# SCH.net
KiCad netlist of a schematic drawn in Altium Designer
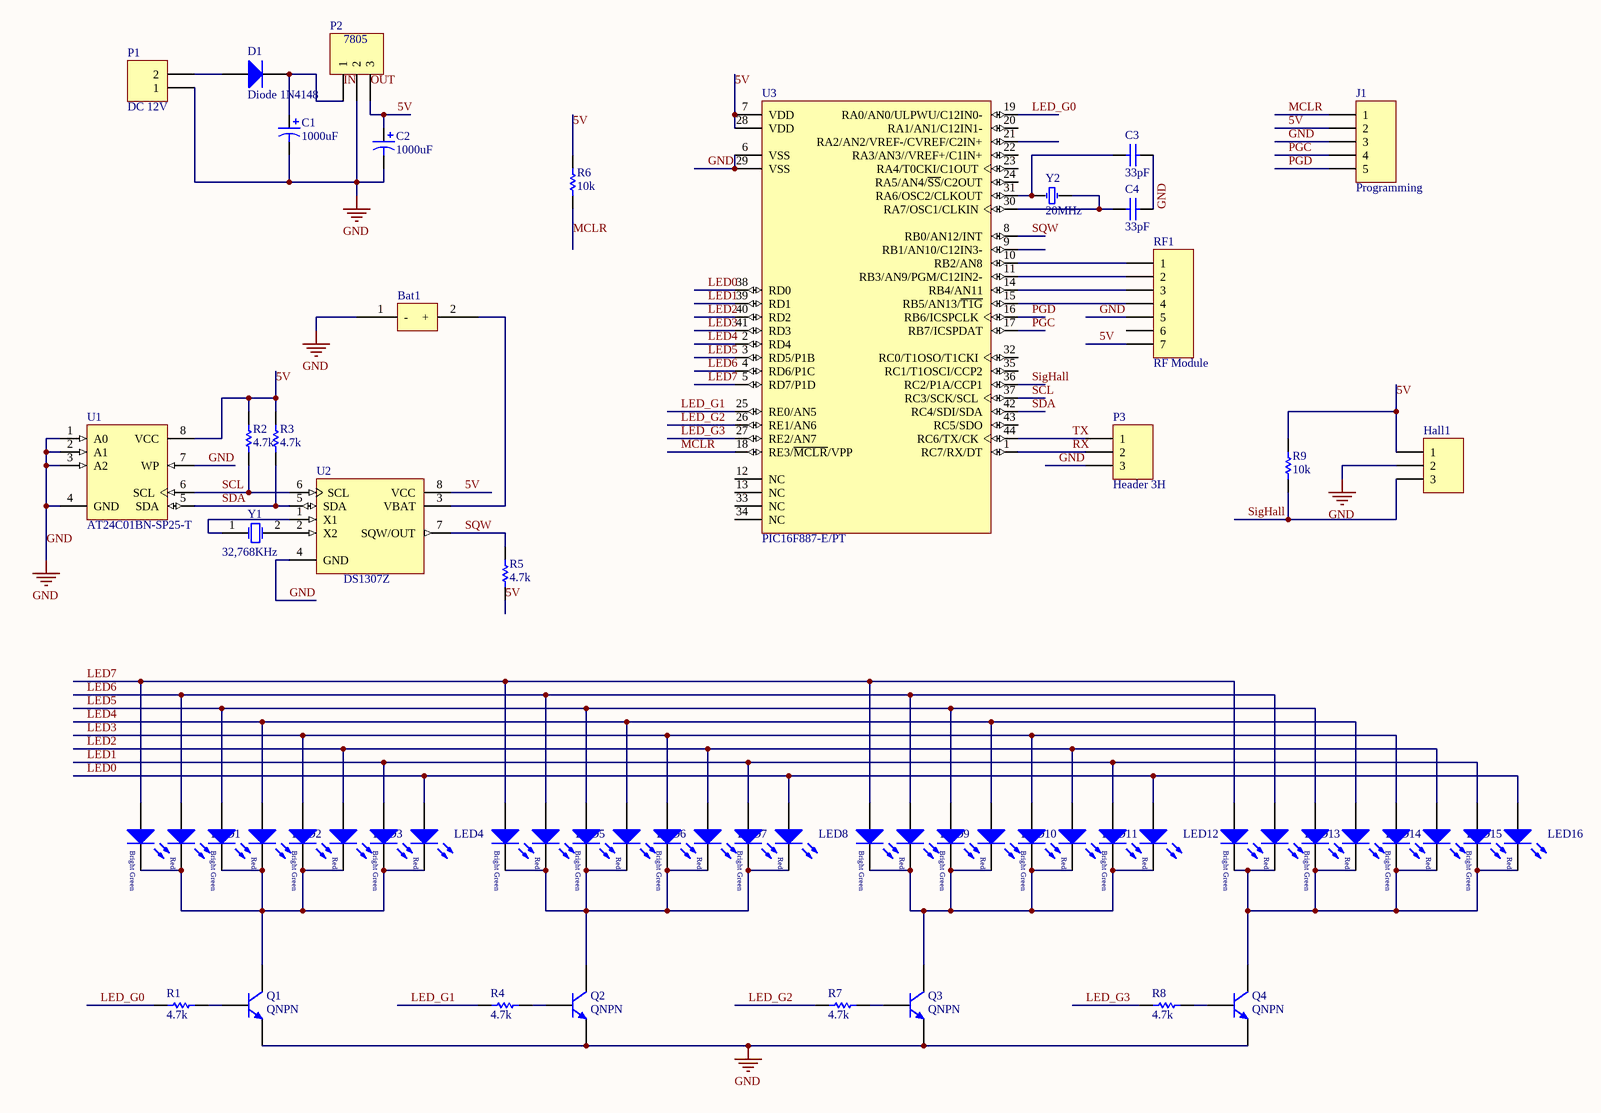
[diagram p0: SCH.SchDoc]

(export (version "E")
  (design (tool "Eeschema 10.0.6"))
  (components
    (comp (ref "Bat1") (value "Battery") (footprint "BATTERY") (libsource (lib "Battery") (part "Battery")))
    (comp (ref "C1")
      (value "1000uF")
      (footprint "CAP POL 2")
      (description "Polarized Capacitor (Surface Mount)")
      (fields (field (name "Comment") "Cap Pol3") (field (name "PUBLISHER") "Altium Limited"))
      (libsource (lib "Miscellaneous Devices") (part "Cap Pol3"))
    )
    (comp (ref "C2")
      (value "1000uF")
      (footprint "CAP POL 2")
      (description "Polarized Capacitor (Surface Mount)")
      (fields (field (name "Comment") "Cap Pol3") (field (name "PUBLISHER") "Altium Limited"))
      (libsource (lib "Miscellaneous Devices") (part "Cap Pol3"))
    )
    (comp (ref "C3")
      (value "33pF")
      (footprint "SM/C_0805")
      (description "Capacitor (Semiconductor SIM Model)")
      (fields (field (name "Comment") "Cap Semi") (field (name "PUBLISHER") "Altium Limited"))
      (libsource (lib "Miscellaneous Devices") (part "Cap Semi"))
    )
    (comp (ref "C4")
      (value "33pF")
      (footprint "SM/C_0805")
      (description "Capacitor (Semiconductor SIM Model)")
      (fields (field (name "Comment") "Cap Semi") (field (name "PUBLISHER") "Altium Limited"))
      (libsource (lib "Miscellaneous Devices") (part "Cap Semi"))
    )
    (comp (ref "D1")
      (value "Diode 1N4148")
      (footprint "DO-35")
      (description "High Conductance Fast Diode")
      (fields (field (name "PUBLISHER") "Altium Limited"))
      (libsource (lib "Miscellaneous Devices") (part "Diode 1N4148"))
    )
    (comp (ref "Hall1")
      (value "Header 3")
      (footprint "HDR1X3")
      (description "Header, 3-Pin")
      (fields (field (name "PUBLISHER") "Altium Limited"))
      (libsource (lib "Miscellaneous Connectors") (part "Header 3"))
    )
    (comp (ref "J1")
      (value "Programming")
      (footprint "HDR1X5H")
      (description "Header, 5-Pin, Right Angle")
      (fields (field (name "PUBLISHER") "Altium Limited"))
      (libsource (lib "Miscellaneous Connectors") (part "Header 5H"))
    )
    (comp (ref "LED1")
      (value "150141RV73100")
      (footprint "3528")
      (description "SMD Bi-Color Top LED, WL-SBTW, Red & Bright Green")
      (fields
        (field (name "MANUFACTURER") "Würth Elektronik eiSos GmbH")
        (field (name "CREATED BY") "Christin Otto")
      )
      (libsource (lib "Altium_WE_eiSos_WL-SBTW") (part "WL-SBTW 3528 150141RV73100"))
    )
    (comp (ref "LED2")
      (value "150141RV73100")
      (footprint "3528")
      (description "SMD Bi-Color Top LED, WL-SBTW, Red & Bright Green")
      (fields
        (field (name "MANUFACTURER") "Würth Elektronik eiSos GmbH")
        (field (name "CREATED BY") "Christin Otto")
      )
      (libsource (lib "Altium_WE_eiSos_WL-SBTW") (part "WL-SBTW 3528 150141RV73100"))
    )
    (comp (ref "LED3")
      (value "150141RV73100")
      (footprint "3528")
      (description "SMD Bi-Color Top LED, WL-SBTW, Red & Bright Green")
      (fields
        (field (name "MANUFACTURER") "Würth Elektronik eiSos GmbH")
        (field (name "CREATED BY") "Christin Otto")
      )
      (libsource (lib "Altium_WE_eiSos_WL-SBTW") (part "WL-SBTW 3528 150141RV73100"))
    )
    (comp (ref "LED4")
      (value "150141RV73100")
      (footprint "3528")
      (description "SMD Bi-Color Top LED, WL-SBTW, Red & Bright Green")
      (fields
        (field (name "MANUFACTURER") "Würth Elektronik eiSos GmbH")
        (field (name "CREATED BY") "Christin Otto")
      )
      (libsource (lib "Altium_WE_eiSos_WL-SBTW") (part "WL-SBTW 3528 150141RV73100"))
    )
    (comp (ref "LED5")
      (value "150141RV73100")
      (footprint "3528")
      (description "SMD Bi-Color Top LED, WL-SBTW, Red & Bright Green")
      (fields
        (field (name "MANUFACTURER") "Würth Elektronik eiSos GmbH")
        (field (name "CREATED BY") "Christin Otto")
      )
      (libsource (lib "Altium_WE_eiSos_WL-SBTW") (part "WL-SBTW 3528 150141RV73100"))
    )
    (comp (ref "LED6")
      (value "150141RV73100")
      (footprint "3528")
      (description "SMD Bi-Color Top LED, WL-SBTW, Red & Bright Green")
      (fields
        (field (name "MANUFACTURER") "Würth Elektronik eiSos GmbH")
        (field (name "CREATED BY") "Christin Otto")
      )
      (libsource (lib "Altium_WE_eiSos_WL-SBTW") (part "WL-SBTW 3528 150141RV73100"))
    )
    (comp (ref "LED7")
      (value "150141RV73100")
      (footprint "3528")
      (description "SMD Bi-Color Top LED, WL-SBTW, Red & Bright Green")
      (fields
        (field (name "MANUFACTURER") "Würth Elektronik eiSos GmbH")
        (field (name "CREATED BY") "Christin Otto")
      )
      (libsource (lib "Altium_WE_eiSos_WL-SBTW") (part "WL-SBTW 3528 150141RV73100"))
    )
    (comp (ref "LED8")
      (value "150141RV73100")
      (footprint "3528")
      (description "SMD Bi-Color Top LED, WL-SBTW, Red & Bright Green")
      (fields
        (field (name "MANUFACTURER") "Würth Elektronik eiSos GmbH")
        (field (name "CREATED BY") "Christin Otto")
      )
      (libsource (lib "Altium_WE_eiSos_WL-SBTW") (part "WL-SBTW 3528 150141RV73100"))
    )
    (comp (ref "LED9")
      (value "150141RV73100")
      (footprint "3528")
      (description "SMD Bi-Color Top LED, WL-SBTW, Red & Bright Green")
      (fields
        (field (name "MANUFACTURER") "Würth Elektronik eiSos GmbH")
        (field (name "CREATED BY") "Christin Otto")
      )
      (libsource (lib "Altium_WE_eiSos_WL-SBTW") (part "WL-SBTW 3528 150141RV73100"))
    )
    (comp (ref "LED10")
      (value "150141RV73100")
      (footprint "3528")
      (description "SMD Bi-Color Top LED, WL-SBTW, Red & Bright Green")
      (fields
        (field (name "MANUFACTURER") "Würth Elektronik eiSos GmbH")
        (field (name "CREATED BY") "Christin Otto")
      )
      (libsource (lib "Altium_WE_eiSos_WL-SBTW") (part "WL-SBTW 3528 150141RV73100"))
    )
    (comp (ref "LED11")
      (value "150141RV73100")
      (footprint "3528")
      (description "SMD Bi-Color Top LED, WL-SBTW, Red & Bright Green")
      (fields
        (field (name "MANUFACTURER") "Würth Elektronik eiSos GmbH")
        (field (name "CREATED BY") "Christin Otto")
      )
      (libsource (lib "Altium_WE_eiSos_WL-SBTW") (part "WL-SBTW 3528 150141RV73100"))
    )
    (comp (ref "LED12")
      (value "150141RV73100")
      (footprint "3528")
      (description "SMD Bi-Color Top LED, WL-SBTW, Red & Bright Green")
      (fields
        (field (name "MANUFACTURER") "Würth Elektronik eiSos GmbH")
        (field (name "CREATED BY") "Christin Otto")
      )
      (libsource (lib "Altium_WE_eiSos_WL-SBTW") (part "WL-SBTW 3528 150141RV73100"))
    )
    (comp (ref "LED13")
      (value "150141RV73100")
      (footprint "3528")
      (description "SMD Bi-Color Top LED, WL-SBTW, Red & Bright Green")
      (fields
        (field (name "MANUFACTURER") "Würth Elektronik eiSos GmbH")
        (field (name "CREATED BY") "Christin Otto")
      )
      (libsource (lib "Altium_WE_eiSos_WL-SBTW") (part "WL-SBTW 3528 150141RV73100"))
    )
    (comp (ref "LED14")
      (value "150141RV73100")
      (footprint "3528")
      (description "SMD Bi-Color Top LED, WL-SBTW, Red & Bright Green")
      (fields
        (field (name "MANUFACTURER") "Würth Elektronik eiSos GmbH")
        (field (name "CREATED BY") "Christin Otto")
      )
      (libsource (lib "Altium_WE_eiSos_WL-SBTW") (part "WL-SBTW 3528 150141RV73100"))
    )
    (comp (ref "LED15")
      (value "150141RV73100")
      (footprint "3528")
      (description "SMD Bi-Color Top LED, WL-SBTW, Red & Bright Green")
      (fields
        (field (name "MANUFACTURER") "Würth Elektronik eiSos GmbH")
        (field (name "CREATED BY") "Christin Otto")
      )
      (libsource (lib "Altium_WE_eiSos_WL-SBTW") (part "WL-SBTW 3528 150141RV73100"))
    )
    (comp (ref "LED16")
      (value "150141RV73100")
      (footprint "3528")
      (description "SMD Bi-Color Top LED, WL-SBTW, Red & Bright Green")
      (fields
        (field (name "MANUFACTURER") "Würth Elektronik eiSos GmbH")
        (field (name "CREATED BY") "Christin Otto")
      )
      (libsource (lib "Altium_WE_eiSos_WL-SBTW") (part "WL-SBTW 3528 150141RV73100"))
    )
    (comp (ref "P1")
      (value "DC 12V")
      (footprint "HDR1X2H")
      (description "Header, 2-Pin, Right Angle")
      (fields (field (name "PUBLISHER") "Altium Limited"))
      (libsource (lib "Miscellaneous Connectors") (part "Header 2H"))
    )
    (comp (ref "P2")
      (value "7805")
      (footprint "HDR1X3")
      (description "Header, 3-Pin")
      (fields (field (name "PUBLISHER") "Altium Limited"))
      (libsource (lib "") (part "Header 3_1"))
    )
    (comp (ref "P3")
      (value "Header 3H")
      (footprint "HDR1X3H")
      (description "Header, 3-Pin, Right Angle")
      (fields (field (name "PUBLISHER") "Altium Limited"))
      (libsource (lib "Miscellaneous Connectors") (part "Header 3H"))
    )
    (comp (ref "Q1")
      (value "QNPN")
      (footprint "SOT-23B_N")
      (description "NPN Bipolar Transistor")
      (fields (field (name "PUBLISHER") "Altium Limited"))
      (libsource (lib "Miscellaneous Devices") (part "QNPN"))
    )
    (comp (ref "Q2")
      (value "QNPN")
      (footprint "SOT-23B_N")
      (description "NPN Bipolar Transistor")
      (fields (field (name "PUBLISHER") "Altium Limited"))
      (libsource (lib "Miscellaneous Devices") (part "QNPN"))
    )
    (comp (ref "Q3")
      (value "QNPN")
      (footprint "SOT-23B_N")
      (description "NPN Bipolar Transistor")
      (fields (field (name "PUBLISHER") "Altium Limited"))
      (libsource (lib "Miscellaneous Devices") (part "QNPN"))
    )
    (comp (ref "Q4")
      (value "QNPN")
      (footprint "SOT-23B_N")
      (description "NPN Bipolar Transistor")
      (fields (field (name "PUBLISHER") "Altium Limited"))
      (libsource (lib "Miscellaneous Devices") (part "QNPN"))
    )
    (comp (ref "R1")
      (value "4.7k")
      (footprint "SM/C_0805")
      (description "Semiconductor Resistor")
      (fields (field (name "Comment") "Res Semi") (field (name "PUBLISHER") "Altium Limited"))
      (libsource (lib "Miscellaneous Devices") (part "Res Semi"))
    )
    (comp (ref "R2")
      (value "4.7k")
      (footprint "SM/C_0805")
      (description "Semiconductor Resistor")
      (fields (field (name "Comment") "Res Semi") (field (name "PUBLISHER") "Altium Limited"))
      (libsource (lib "Miscellaneous Devices") (part "Res Semi"))
    )
    (comp (ref "R3")
      (value "4.7k")
      (footprint "SM/C_0805")
      (description "Semiconductor Resistor")
      (fields (field (name "Comment") "Res Semi") (field (name "PUBLISHER") "Altium Limited"))
      (libsource (lib "Miscellaneous Devices") (part "Res Semi"))
    )
    (comp (ref "R4")
      (value "4.7k")
      (footprint "SM/C_0805")
      (description "Semiconductor Resistor")
      (fields (field (name "Comment") "Res Semi") (field (name "PUBLISHER") "Altium Limited"))
      (libsource (lib "Miscellaneous Devices") (part "Res Semi"))
    )
    (comp (ref "R5")
      (value "4.7k")
      (footprint "SM/C_0805")
      (description "Semiconductor Resistor")
      (fields (field (name "Comment") "Res Semi") (field (name "PUBLISHER") "Altium Limited"))
      (libsource (lib "Miscellaneous Devices") (part "Res Semi"))
    )
    (comp (ref "R6")
      (value "10k")
      (footprint "SM/C_0805")
      (description "Semiconductor Resistor")
      (fields (field (name "Comment") "Res Semi") (field (name "PUBLISHER") "Altium Limited"))
      (libsource (lib "Miscellaneous Devices") (part "Res Semi"))
    )
    (comp (ref "R7")
      (value "4.7k")
      (footprint "SM/C_0805")
      (description "Semiconductor Resistor")
      (fields (field (name "Comment") "Res Semi") (field (name "PUBLISHER") "Altium Limited"))
      (libsource (lib "Miscellaneous Devices") (part "Res Semi"))
    )
    (comp (ref "R8")
      (value "4.7k")
      (footprint "SM/C_0805")
      (description "Semiconductor Resistor")
      (fields (field (name "Comment") "Res Semi") (field (name "PUBLISHER") "Altium Limited"))
      (libsource (lib "Miscellaneous Devices") (part "Res Semi"))
    )
    (comp (ref "R9")
      (value "10k")
      (footprint "SM/C_0805")
      (description "Semiconductor Resistor")
      (fields (field (name "Comment") "Res Semi") (field (name "PUBLISHER") "Altium Limited"))
      (libsource (lib "Miscellaneous Devices") (part "Res Semi"))
    )
    (comp (ref "RF1")
      (value "RF Module")
      (footprint "HDR1X7")
      (description "Header, 7-Pin")
      (fields (field (name "PUBLISHER") "Altium Limited"))
      (libsource (lib "Miscellaneous Connectors") (part "Header 7"))
    )
    (comp (ref "U1")
      (value "AT24C01BN-SP25-T")
      (footprint "8S1_N")
      (fields (field (name "PUBLISHER") "Altium Limited"))
      (libsource (lib "Atmel Memory Serial EEPROM") (part "AT24C01BN-SP25-T"))
    )
    (comp (ref "U2")
      (value "DS1307Z")
      (footprint "SOIC8N_N")
      (description "64 X 8 Serial Real-Time Clock")
      (fields (field (name "PUBLISHER") "Altium Limited"))
      (libsource (lib "Dallas Peripheral Real Time Clock") (part "DS1307Z"))
    )
    (comp (ref "U3")
      (value "PIC16F887-E/PT")
      (footprint "TQFP-PT44_N")
      (fields (field (name "PUBLISHER") "Altium Limited"))
      (libsource (lib "Microchip Microcontroller 8-Bit PIC16") (part "PIC16F887-E/PT"))
    )
    (comp (ref "Y1")
      (value "32,768KHz")
      (footprint "CFPX-93")
      (description "Surface Mount Quartz Crystal")
      (fields (field (name "PUBLISHER") "Altium Limited"))
      (libsource (lib "C-MAC Crystal Oscillator") (part "CFPX-93"))
    )
    (comp (ref "Y2") (value "20MHz") (footprint "CRYSTAL") (libsource (lib "FUFO") (part "XTAL")))
  )
  (nets
    (net (code "1") (name "/5V") (class "Default")
      (node (ref "C2") (pin "1") (pinfunction "1_1") (pintype "passive"))
      (node (ref "Hall1") (pin "1") (pinfunction "1_1") (pintype "passive"))
      (node (ref "J1") (pin "2") (pinfunction "2_2") (pintype "passive"))
      (node (ref "P2") (pin "3") (pinfunction "3_3") (pintype "passive"))
      (node (ref "R2") (pin "2") (pinfunction "2_2") (pintype "passive"))
      (node (ref "R3") (pin "2") (pinfunction "2_2") (pintype "passive"))
      (node (ref "R5") (pin "1") (pinfunction "1_1") (pintype "passive"))
      (node (ref "R6") (pin "2") (pinfunction "2_2") (pintype "passive"))
      (node (ref "R9") (pin "2") (pinfunction "2_2") (pintype "passive"))
      (node (ref "RF1") (pin "7") (pinfunction "7_7") (pintype "passive"))
      (node (ref "U1") (pin "8") (pinfunction "VCC_8") (pintype "power_in"))
      (node (ref "U2") (pin "8") (pinfunction "VCC_8") (pintype "power_in"))
      (node (ref "U3") (pin "28") (pinfunction "VDD_28") (pintype "power_in"))
      (node (ref "U3") (pin "7") (pinfunction "VDD_7") (pintype "power_in"))
    )
    (net (code "3") (name "/LED0") (class "Default")
      (node (ref "LED12") (pin "1") (pinfunction "A_1") (pintype "passive"))
      (node (ref "LED16") (pin "1") (pinfunction "A_1") (pintype "passive"))
      (node (ref "LED4") (pin "1") (pinfunction "A_1") (pintype "passive"))
      (node (ref "LED8") (pin "1") (pinfunction "A_1") (pintype "passive"))
      (node (ref "U3") (pin "38") (pinfunction "RD0_38") (pintype "bidirectional"))
    )
    (net (code "4") (name "/LED1") (class "Default")
      (node (ref "LED12") (pin "2") (pinfunction "A_2") (pintype "passive"))
      (node (ref "LED16") (pin "2") (pinfunction "A_2") (pintype "passive"))
      (node (ref "LED4") (pin "2") (pinfunction "A_2") (pintype "passive"))
      (node (ref "LED8") (pin "2") (pinfunction "A_2") (pintype "passive"))
      (node (ref "U3") (pin "39") (pinfunction "RD1_39") (pintype "bidirectional"))
    )
    (net (code "5") (name "/LED2") (class "Default")
      (node (ref "LED11") (pin "1") (pinfunction "A_1") (pintype "passive"))
      (node (ref "LED15") (pin "1") (pinfunction "A_1") (pintype "passive"))
      (node (ref "LED3") (pin "1") (pinfunction "A_1") (pintype "passive"))
      (node (ref "LED7") (pin "1") (pinfunction "A_1") (pintype "passive"))
      (node (ref "U3") (pin "40") (pinfunction "RD2_40") (pintype "bidirectional"))
    )
    (net (code "6") (name "/LED3") (class "Default")
      (node (ref "LED11") (pin "2") (pinfunction "A_2") (pintype "passive"))
      (node (ref "LED15") (pin "2") (pinfunction "A_2") (pintype "passive"))
      (node (ref "LED3") (pin "2") (pinfunction "A_2") (pintype "passive"))
      (node (ref "LED7") (pin "2") (pinfunction "A_2") (pintype "passive"))
      (node (ref "U3") (pin "41") (pinfunction "RD3_41") (pintype "bidirectional"))
    )
    (net (code "7") (name "/LED4") (class "Default")
      (node (ref "LED10") (pin "1") (pinfunction "A_1") (pintype "passive"))
      (node (ref "LED14") (pin "1") (pinfunction "A_1") (pintype "passive"))
      (node (ref "LED2") (pin "1") (pinfunction "A_1") (pintype "passive"))
      (node (ref "LED6") (pin "1") (pinfunction "A_1") (pintype "passive"))
      (node (ref "U3") (pin "2") (pinfunction "RD4_2") (pintype "bidirectional"))
    )
    (net (code "8") (name "/LED5") (class "Default")
      (node (ref "LED10") (pin "2") (pinfunction "A_2") (pintype "passive"))
      (node (ref "LED14") (pin "2") (pinfunction "A_2") (pintype "passive"))
      (node (ref "LED2") (pin "2") (pinfunction "A_2") (pintype "passive"))
      (node (ref "LED6") (pin "2") (pinfunction "A_2") (pintype "passive"))
      (node (ref "U3") (pin "3") (pinfunction "RD5/P1B_3") (pintype "bidirectional"))
    )
    (net (code "9") (name "/LED6") (class "Default")
      (node (ref "LED1") (pin "1") (pinfunction "A_1") (pintype "passive"))
      (node (ref "LED13") (pin "1") (pinfunction "A_1") (pintype "passive"))
      (node (ref "LED5") (pin "1") (pinfunction "A_1") (pintype "passive"))
      (node (ref "LED9") (pin "1") (pinfunction "A_1") (pintype "passive"))
      (node (ref "U3") (pin "4") (pinfunction "RD6/P1C_4") (pintype "bidirectional"))
    )
    (net (code "10") (name "/LED7") (class "Default")
      (node (ref "LED1") (pin "2") (pinfunction "A_2") (pintype "passive"))
      (node (ref "LED13") (pin "2") (pinfunction "A_2") (pintype "passive"))
      (node (ref "LED5") (pin "2") (pinfunction "A_2") (pintype "passive"))
      (node (ref "LED9") (pin "2") (pinfunction "A_2") (pintype "passive"))
      (node (ref "U3") (pin "5") (pinfunction "RD7/P1D_5") (pintype "bidirectional"))
    )
    (net (code "11") (name "/LED_G0") (class "Default")
      (node (ref "R1") (pin "2") (pinfunction "2_2") (pintype "passive"))
      (node (ref "U3") (pin "19") (pinfunction "RA0/AN0/ULPWU/C12IN0-_19") (pintype "bidirectional"))
    )
    (net (code "12") (name "/LED_G1") (class "Default")
      (node (ref "R4") (pin "2") (pinfunction "2_2") (pintype "passive"))
      (node (ref "U3") (pin "25") (pinfunction "RE0/AN5_25") (pintype "bidirectional"))
    )
    (net (code "13") (name "/LED_G2") (class "Default")
      (node (ref "R7") (pin "2") (pinfunction "2_2") (pintype "passive"))
      (node (ref "U3") (pin "26") (pinfunction "RE1/AN6_26") (pintype "bidirectional"))
    )
    (net (code "14") (name "/LED_G3") (class "Default")
      (node (ref "R8") (pin "2") (pinfunction "2_2") (pintype "passive"))
      (node (ref "U3") (pin "27") (pinfunction "RE2/AN7_27") (pintype "bidirectional"))
    )
    (net (code "15") (name "/MCLR") (class "Default")
      (node (ref "J1") (pin "1") (pinfunction "1_1") (pintype "passive"))
      (node (ref "R6") (pin "1") (pinfunction "1_1") (pintype "passive"))
      (node (ref "U3") (pin "18") (pinfunction "RE3/~{MCLR}/VPP_18") (pintype "bidirectional"))
    )
    (net (code "17") (name "/PGC") (class "Default")
      (node (ref "J1") (pin "4") (pinfunction "4_4") (pintype "passive"))
      (node (ref "U3") (pin "17") (pinfunction "RB7/ICSPDAT_17") (pintype "bidirectional"))
    )
    (net (code "18") (name "/PGD") (class "Default")
      (node (ref "J1") (pin "5") (pinfunction "5_5") (pintype "passive"))
      (node (ref "U3") (pin "16") (pinfunction "RB6/ICSPCLK_16") (pintype "bidirectional"))
    )
    (net (code "19") (name "/RX") (class "Default")
      (node (ref "P3") (pin "2") (pinfunction "2_2") (pintype "passive"))
      (node (ref "U3") (pin "1") (pinfunction "RC7/RX/DT_1") (pintype "bidirectional"))
    )
    (net (code "20") (name "/SCL") (class "Default")
      (node (ref "R2") (pin "1") (pinfunction "1_1") (pintype "passive"))
      (node (ref "U1") (pin "6") (pinfunction "SCL_6") (pintype "input"))
      (node (ref "U2") (pin "6") (pinfunction "SCL_6") (pintype "input"))
      (node (ref "U3") (pin "37") (pinfunction "RC3/SCK/SCL_37") (pintype "bidirectional"))
    )
    (net (code "21") (name "/SDA") (class "Default")
      (node (ref "R3") (pin "1") (pinfunction "1_1") (pintype "passive"))
      (node (ref "U1") (pin "5") (pinfunction "SDA_5") (pintype "bidirectional"))
      (node (ref "U2") (pin "5") (pinfunction "SDA_5") (pintype "bidirectional"))
      (node (ref "U3") (pin "42") (pinfunction "RC4/SDI/SDA_42") (pintype "bidirectional"))
    )
    (net (code "22") (name "/SQW") (class "Default")
      (node (ref "R5") (pin "2") (pinfunction "2_2") (pintype "passive"))
      (node (ref "U2") (pin "7") (pinfunction "SQW/OUT_7") (pintype "output"))
      (node (ref "U3") (pin "8") (pinfunction "RB0/AN12/INT_8") (pintype "bidirectional"))
    )
    (net (code "23") (name "/SigHall") (class "Default")
      (node (ref "Hall1") (pin "3") (pinfunction "3_3") (pintype "passive"))
      (node (ref "R9") (pin "1") (pinfunction "1_1") (pintype "passive"))
      (node (ref "U3") (pin "36") (pinfunction "RC2/P1A/CCP1_36") (pintype "bidirectional"))
    )
    (net (code "24") (name "/TX") (class "Default")
      (node (ref "P3") (pin "1") (pinfunction "1_1") (pintype "passive"))
      (node (ref "U3") (pin "44") (pinfunction "RC6/TX/CK_44") (pintype "bidirectional"))
    )
    (net (code "25") (name "GND") (class "Default")
      (node (ref "Bat1") (pin "1") (pinfunction "-_1") (pintype "passive"))
      (node (ref "C1") (pin "2") (pinfunction "2_2") (pintype "passive"))
      (node (ref "C2") (pin "2") (pinfunction "2_2") (pintype "passive"))
      (node (ref "C3") (pin "1") (pinfunction "1_1") (pintype "passive"))
      (node (ref "C4") (pin "1") (pinfunction "1_1") (pintype "passive"))
      (node (ref "Hall1") (pin "2") (pinfunction "2_2") (pintype "passive"))
      (node (ref "J1") (pin "3") (pinfunction "3_3") (pintype "passive"))
      (node (ref "P1") (pin "1") (pinfunction "1_1") (pintype "passive"))
      (node (ref "P2") (pin "2") (pinfunction "2_2") (pintype "passive"))
      (node (ref "P3") (pin "3") (pinfunction "3_3") (pintype "passive"))
      (node (ref "Q1") (pin "3") (pinfunction "E_3") (pintype "passive"))
      (node (ref "Q2") (pin "3") (pinfunction "E_3") (pintype "passive"))
      (node (ref "Q3") (pin "3") (pinfunction "E_3") (pintype "passive"))
      (node (ref "Q4") (pin "3") (pinfunction "E_3") (pintype "passive"))
      (node (ref "RF1") (pin "5") (pinfunction "5_5") (pintype "passive"))
      (node (ref "U1") (pin "1") (pinfunction "A0_1") (pintype "input"))
      (node (ref "U1") (pin "2") (pinfunction "A1_2") (pintype "input"))
      (node (ref "U1") (pin "3") (pinfunction "A2_3") (pintype "input"))
      (node (ref "U1") (pin "4") (pinfunction "GND_4") (pintype "power_in"))
      (node (ref "U1") (pin "7") (pinfunction "WP_7") (pintype "input"))
      (node (ref "U2") (pin "4") (pinfunction "GND_4") (pintype "power_in"))
      (node (ref "U3") (pin "29") (pinfunction "VSS_29") (pintype "power_in"))
      (node (ref "U3") (pin "6") (pinfunction "VSS_6") (pintype "power_in"))
    )
    (net (code "26") (name "Net-(Bat1-+)") (class "Default")
      (node (ref "Bat1") (pin "2") (pinfunction "+_2") (pintype "passive"))
      (node (ref "U2") (pin "3") (pinfunction "VBAT_3") (pintype "power_in"))
    )
    (net (code "27") (name "Net-(D1-A)") (class "Default")
      (node (ref "D1") (pin "1") (pinfunction "A_1") (pintype "passive"))
      (node (ref "P1") (pin "2") (pinfunction "2_2") (pintype "passive"))
    )
    (net (code "28") (name "Net-(D1-K)") (class "Default")
      (node (ref "C1") (pin "1") (pinfunction "1_1") (pintype "passive"))
      (node (ref "D1") (pin "2") (pinfunction "K_2") (pintype "passive"))
      (node (ref "P2") (pin "1") (pinfunction "1_1") (pintype "passive"))
    )
    (net (code "29") (name "Net-(Q1-B)") (class "Default")
      (node (ref "Q1") (pin "2") (pinfunction "B_2") (pintype "passive"))
      (node (ref "R1") (pin "1") (pinfunction "1_1") (pintype "passive"))
    )
    (net (code "30") (name "Net-(Q1-C)") (class "Default")
      (node (ref "LED1") (pin "3") (pinfunction "C_3") (pintype "passive"))
      (node (ref "LED1") (pin "4") (pinfunction "C_4") (pintype "passive"))
      (node (ref "LED2") (pin "3") (pinfunction "C_3") (pintype "passive"))
      (node (ref "LED2") (pin "4") (pinfunction "C_4") (pintype "passive"))
      (node (ref "LED3") (pin "3") (pinfunction "C_3") (pintype "passive"))
      (node (ref "LED3") (pin "4") (pinfunction "C_4") (pintype "passive"))
      (node (ref "LED4") (pin "3") (pinfunction "C_3") (pintype "passive"))
      (node (ref "LED4") (pin "4") (pinfunction "C_4") (pintype "passive"))
      (node (ref "Q1") (pin "1") (pinfunction "C_1") (pintype "passive"))
    )
    (net (code "31") (name "Net-(Q2-B)") (class "Default")
      (node (ref "Q2") (pin "2") (pinfunction "B_2") (pintype "passive"))
      (node (ref "R4") (pin "1") (pinfunction "1_1") (pintype "passive"))
    )
    (net (code "32") (name "Net-(Q2-C)") (class "Default")
      (node (ref "LED5") (pin "3") (pinfunction "C_3") (pintype "passive"))
      (node (ref "LED5") (pin "4") (pinfunction "C_4") (pintype "passive"))
      (node (ref "LED6") (pin "3") (pinfunction "C_3") (pintype "passive"))
      (node (ref "LED6") (pin "4") (pinfunction "C_4") (pintype "passive"))
      (node (ref "LED7") (pin "3") (pinfunction "C_3") (pintype "passive"))
      (node (ref "LED7") (pin "4") (pinfunction "C_4") (pintype "passive"))
      (node (ref "LED8") (pin "3") (pinfunction "C_3") (pintype "passive"))
      (node (ref "LED8") (pin "4") (pinfunction "C_4") (pintype "passive"))
      (node (ref "Q2") (pin "1") (pinfunction "C_1") (pintype "passive"))
    )
    (net (code "33") (name "Net-(Q3-B)") (class "Default")
      (node (ref "Q3") (pin "2") (pinfunction "B_2") (pintype "passive"))
      (node (ref "R7") (pin "1") (pinfunction "1_1") (pintype "passive"))
    )
    (net (code "34") (name "Net-(Q3-C)") (class "Default")
      (node (ref "LED10") (pin "3") (pinfunction "C_3") (pintype "passive"))
      (node (ref "LED10") (pin "4") (pinfunction "C_4") (pintype "passive"))
      (node (ref "LED11") (pin "3") (pinfunction "C_3") (pintype "passive"))
      (node (ref "LED11") (pin "4") (pinfunction "C_4") (pintype "passive"))
      (node (ref "LED12") (pin "3") (pinfunction "C_3") (pintype "passive"))
      (node (ref "LED12") (pin "4") (pinfunction "C_4") (pintype "passive"))
      (node (ref "LED9") (pin "3") (pinfunction "C_3") (pintype "passive"))
      (node (ref "LED9") (pin "4") (pinfunction "C_4") (pintype "passive"))
      (node (ref "Q3") (pin "1") (pinfunction "C_1") (pintype "passive"))
    )
    (net (code "35") (name "Net-(Q4-B)") (class "Default")
      (node (ref "Q4") (pin "2") (pinfunction "B_2") (pintype "passive"))
      (node (ref "R8") (pin "1") (pinfunction "1_1") (pintype "passive"))
    )
    (net (code "36") (name "Net-(Q4-C)") (class "Default")
      (node (ref "LED13") (pin "3") (pinfunction "C_3") (pintype "passive"))
      (node (ref "LED13") (pin "4") (pinfunction "C_4") (pintype "passive"))
      (node (ref "LED14") (pin "3") (pinfunction "C_3") (pintype "passive"))
      (node (ref "LED14") (pin "4") (pinfunction "C_4") (pintype "passive"))
      (node (ref "LED15") (pin "3") (pinfunction "C_3") (pintype "passive"))
      (node (ref "LED15") (pin "4") (pinfunction "C_4") (pintype "passive"))
      (node (ref "LED16") (pin "3") (pinfunction "C_3") (pintype "passive"))
      (node (ref "LED16") (pin "4") (pinfunction "C_4") (pintype "passive"))
      (node (ref "Q4") (pin "1") (pinfunction "C_1") (pintype "passive"))
    )
    (net (code "37") (name "Net-(U2-X1)") (class "Default")
      (node (ref "U2") (pin "1") (pinfunction "X1_1") (pintype "input"))
      (node (ref "Y1") (pin "1") (pinfunction "OSC1_1") (pintype "passive"))
    )
    (net (code "38") (name "Net-(U2-X2)") (class "Default")
      (node (ref "U2") (pin "2") (pinfunction "X2_2") (pintype "input"))
      (node (ref "Y1") (pin "2") (pinfunction "OSC2_2") (pintype "passive"))
    )
    (net (code "39") (name "Net-(U3-RA6{slash}OSC2{slash}CLKOUT)") (class "Default")
      (node (ref "C3") (pin "2") (pinfunction "2_2") (pintype "passive"))
      (node (ref "U3") (pin "31") (pinfunction "RA6/OSC2/CLKOUT_31") (pintype "bidirectional"))
      (node (ref "Y2") (pin "1") (pinfunction "1_1") (pintype "passive"))
    )
    (net (code "40") (name "Net-(U3-RA7{slash}OSC1{slash}CLKIN)") (class "Default")
      (node (ref "C4") (pin "2") (pinfunction "2_2") (pintype "passive"))
      (node (ref "U3") (pin "30") (pinfunction "RA7/OSC1/CLKIN_30") (pintype "bidirectional"))
      (node (ref "Y2") (pin "2") (pinfunction "2_2") (pintype "passive"))
    )
    (net (code "41") (name "Net-(U3-RB2{slash}AN8)") (class "Default")
      (node (ref "RF1") (pin "1") (pinfunction "1_1") (pintype "passive"))
      (node (ref "U3") (pin "10") (pinfunction "RB2/AN8_10") (pintype "bidirectional"))
    )
    (net (code "42") (name "Net-(U3-RB3{slash}AN9{slash}PGM{slash}C12IN2-)") (class "Default")
      (node (ref "RF1") (pin "2") (pinfunction "2_2") (pintype "passive"))
      (node (ref "U3") (pin "11") (pinfunction "RB3/AN9/PGM/C12IN2-_11") (pintype "bidirectional"))
    )
    (net (code "43") (name "Net-(U3-RB4{slash}AN11)") (class "Default")
      (node (ref "RF1") (pin "3") (pinfunction "3_3") (pintype "passive"))
      (node (ref "U3") (pin "14") (pinfunction "RB4/AN11_14") (pintype "bidirectional"))
    )
    (net (code "44") (name "Net-(U3-RB5{slash}AN13{slash}~{T1G})") (class "Default")
      (node (ref "RF1") (pin "4") (pinfunction "4_4") (pintype "passive"))
      (node (ref "U3") (pin "15") (pinfunction "RB5/AN13/~{T1G}_15") (pintype "bidirectional"))
    )
    (net (code "45") (name "unconnected-(RF1-Pad6)") (class "Default")
      (node (ref "RF1") (pin "6") (pinfunction "6_6") (pintype "passive"))
    )
    (net (code "46") (name "unconnected-(U3-NC-Pad12)") (class "Default")
      (node (ref "U3") (pin "12") (pinfunction "NC_12") (pintype "passive"))
    )
    (net (code "47") (name "unconnected-(U3-NC-Pad13)") (class "Default")
      (node (ref "U3") (pin "13") (pinfunction "NC_13") (pintype "passive"))
    )
    (net (code "48") (name "unconnected-(U3-NC-Pad33)") (class "Default")
      (node (ref "U3") (pin "33") (pinfunction "NC_33") (pintype "passive"))
    )
    (net (code "49") (name "unconnected-(U3-NC-Pad34)") (class "Default")
      (node (ref "U3") (pin "34") (pinfunction "NC_34") (pintype "passive"))
    )
    (net (code "50") (name "unconnected-(U3-RA1{slash}AN1{slash}C12IN1--Pad20)") (class "Default")
      (node (ref "U3") (pin "20") (pinfunction "RA1/AN1/C12IN1-_20") (pintype "bidirectional"))
    )
    (net (code "51") (name "unconnected-(U3-RA2{slash}AN2{slash}VREF-{slash}CVREF{slash}C2IN+-Pad21)") (class "Default")
      (node (ref "U3") (pin "21") (pinfunction "RA2/AN2/VREF-/CVREF/C2IN+_21") (pintype "bidirectional"))
    )
    (net (code "52") (name "unconnected-(U3-RA3{slash}AN3{slash}{slash}VREF+{slash}C1IN+-Pad22)") (class "Default")
      (node (ref "U3") (pin "22") (pinfunction "RA3/AN3//VREF+/C1IN+_22") (pintype "bidirectional"))
    )
    (net (code "53") (name "unconnected-(U3-RA4{slash}T0CKI{slash}C1OUT-Pad23)") (class "Default")
      (node (ref "U3") (pin "23") (pinfunction "RA4/T0CKI/C1OUT_23") (pintype "bidirectional"))
    )
    (net (code "54") (name "unconnected-(U3-RA5{slash}AN4{slash}~{SS}{slash}C2OUT-Pad24)") (class "Default")
      (node (ref "U3") (pin "24") (pinfunction "RA5/AN4/~{SS}/C2OUT_24") (pintype "bidirectional"))
    )
    (net (code "55") (name "unconnected-(U3-RB1{slash}AN10{slash}C12IN3--Pad9)") (class "Default")
      (node (ref "U3") (pin "9") (pinfunction "RB1/AN10/C12IN3-_9") (pintype "bidirectional"))
    )
    (net (code "56") (name "unconnected-(U3-RC0{slash}T1OSO{slash}T1CKI-Pad32)") (class "Default")
      (node (ref "U3") (pin "32") (pinfunction "RC0/T1OSO/T1CKI_32") (pintype "bidirectional"))
    )
    (net (code "57") (name "unconnected-(U3-RC1{slash}T1OSCI{slash}CCP2-Pad35)") (class "Default")
      (node (ref "U3") (pin "35") (pinfunction "RC1/T1OSCI/CCP2_35") (pintype "bidirectional"))
    )
    (net (code "58") (name "unconnected-(U3-RC5{slash}SDO-Pad43)") (class "Default")
      (node (ref "U3") (pin "43") (pinfunction "RC5/SDO_43") (pintype "bidirectional"))
    )
  )
)
